# v0_6_2.net
KiCad netlist of a schematic drawn in EAGLE
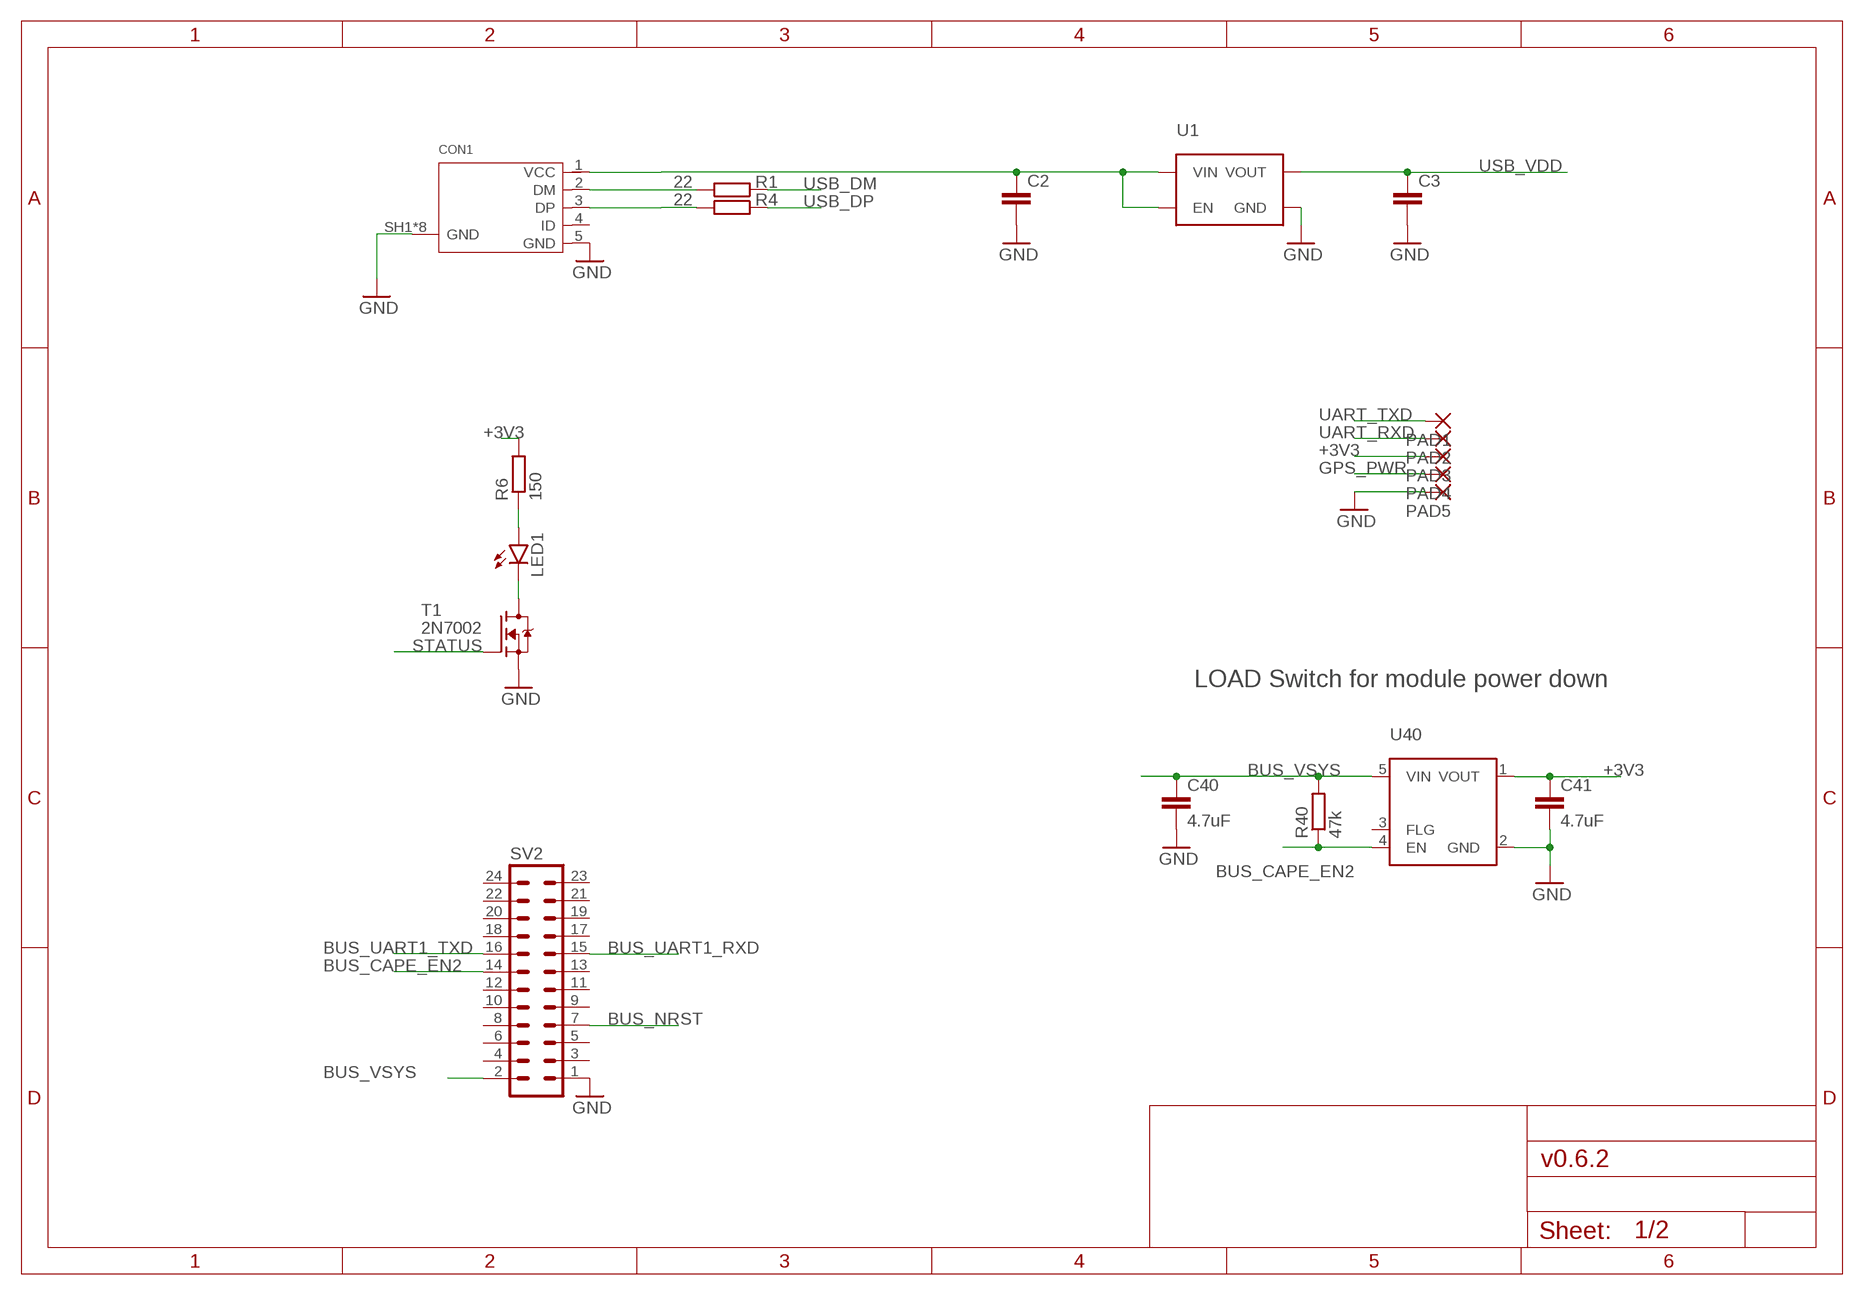
[diagram p0: schematic, sheet 1]
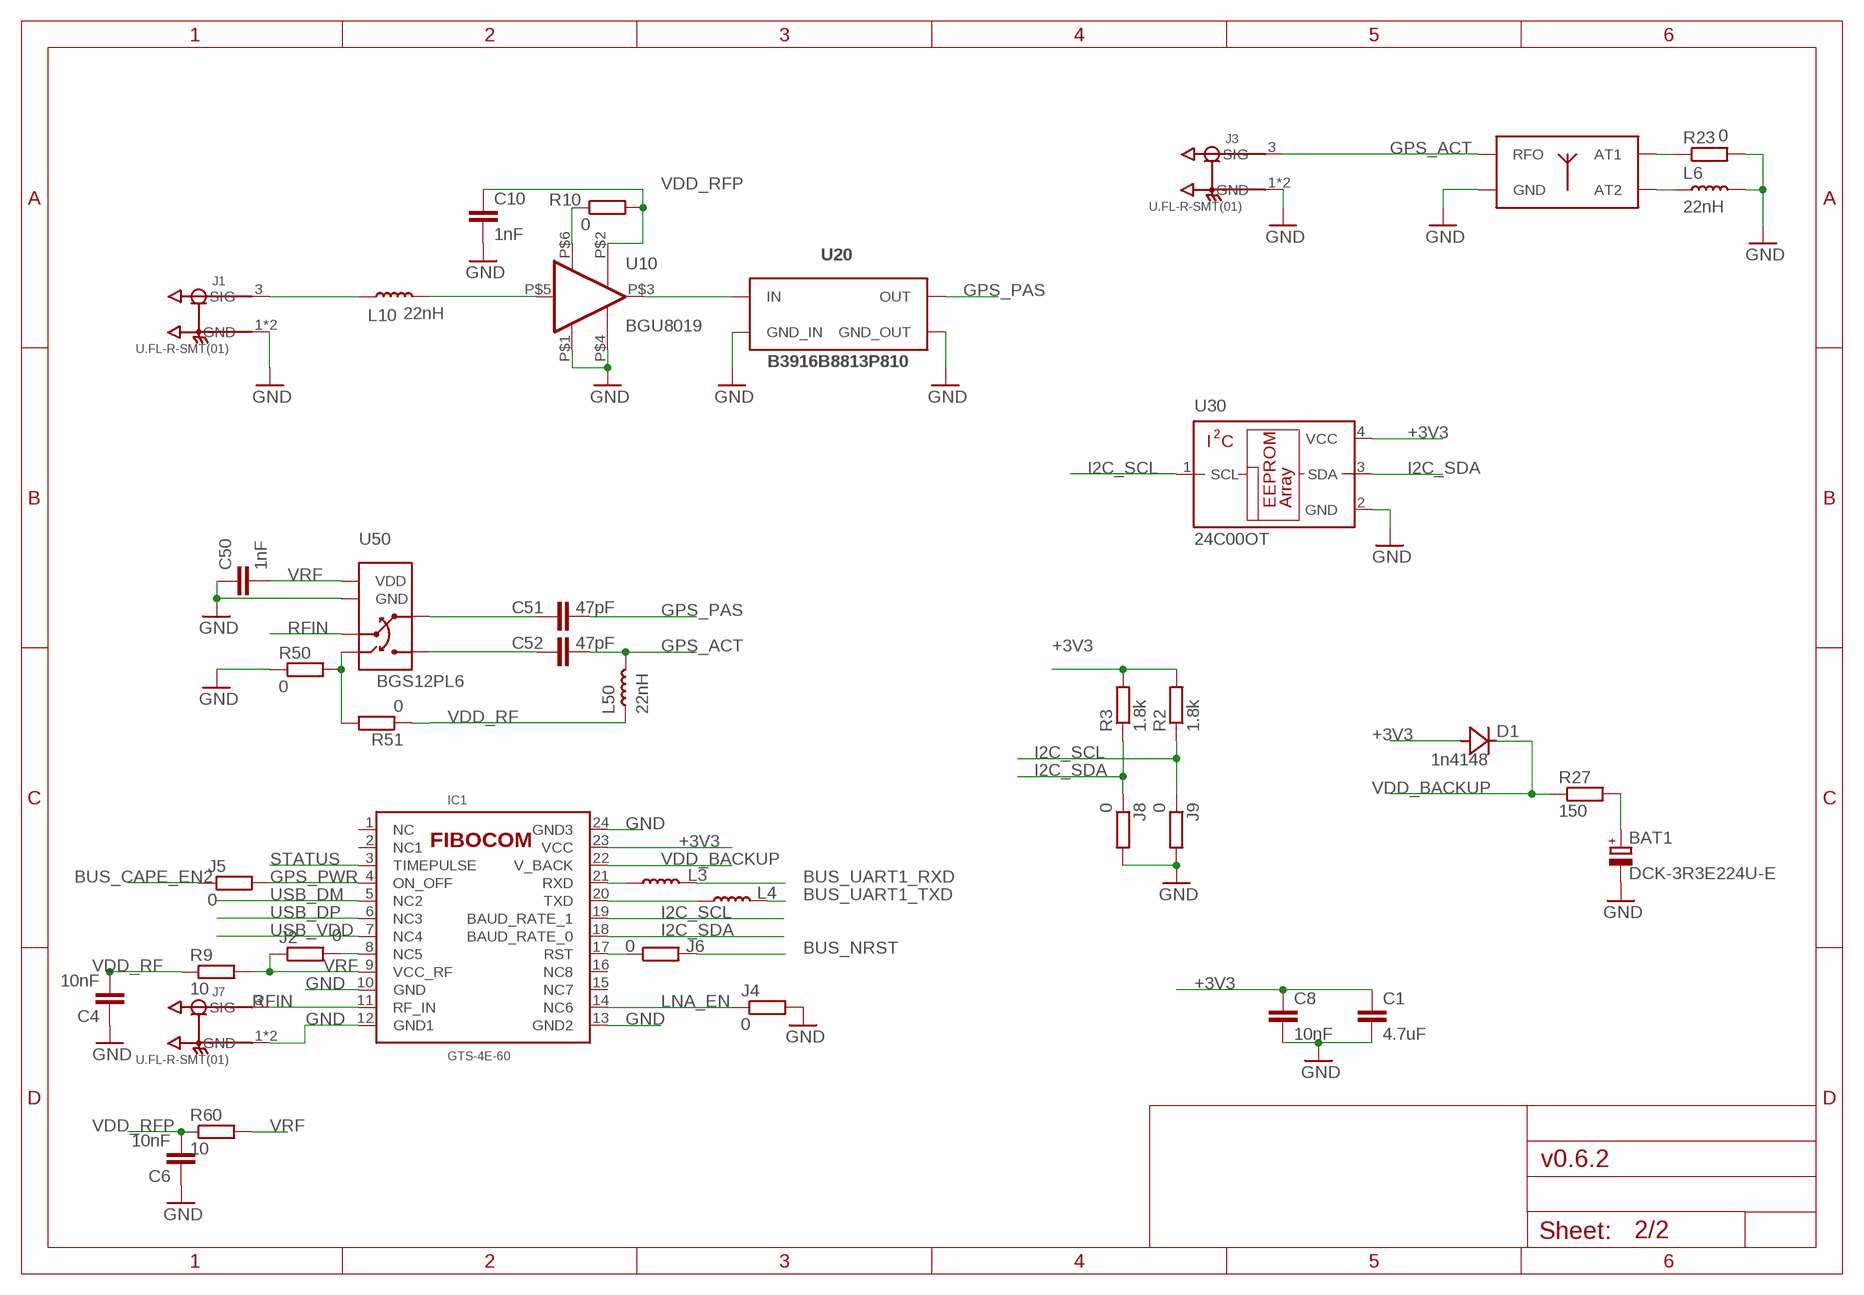
[diagram p1: schematic, sheet 2]

(export (version "E")
  (design (tool "Eeschema 10.0.6"))
  (components
    (comp (ref "ANT1")
      (value "M20047")
      (footprint "eagle-import:PCBCOMPONENT_1")
      (libsource (lib "eagle-import") (part "M20047"))
    )
    (comp (ref "BAT1")
      (value "DCK-3R3E224U-E")
      (footprint "eagle-import:621")
      (libsource (lib "eagle-import") (part "DCK-3R3E224U-E"))
    )
    (comp (ref "C1")
      (value "4.7uF")
      (footprint "eagle-import:C0603")
      (libsource (lib "eagle-import") (part "C-EUC0603"))
    )
    (comp (ref "C4")
      (value "10nF")
      (footprint "eagle-import:C0402K")
      (libsource (lib "eagle-import") (part "CAP-0402"))
    )
    (comp (ref "C6")
      (value "10nF")
      (footprint "eagle-import:C0402K")
      (libsource (lib "eagle-import") (part "CAP-0402"))
    )
    (comp (ref "C8")
      (value "10nF")
      (footprint "eagle-import:C0402K")
      (libsource (lib "eagle-import") (part "CAP-0402"))
    )
    (comp (ref "C10")
      (value "1nF")
      (footprint "eagle-import:C0402K")
      (libsource (lib "eagle-import") (part "CAP-0402"))
    )
    (comp (ref "C50")
      (value "1nF")
      (footprint "eagle-import:C0402K")
      (libsource (lib "eagle-import") (part "CAP-0402"))
    )
    (comp (ref "C51")
      (value "47pF")
      (footprint "eagle-import:C0402K")
      (libsource (lib "eagle-import") (part "CAP-0402"))
    )
    (comp (ref "C52")
      (value "47pF")
      (footprint "eagle-import:C0402K")
      (libsource (lib "eagle-import") (part "CAP-0402"))
    )
    (comp (ref "D1")
      (value "1n4148")
      (footprint "eagle-import:SOD323")
      (libsource (lib "eagle-import") (part "1N4148WS"))
    )
    (comp (ref "IC1")
      (value "GTS-4E-60")
      (footprint "eagle-import:_GTS_4E_60")
      (libsource (lib "eagle-import") (part "GTS-4E-60"))
    )
    (comp (ref "J1")
      (value "U.FL-R-SMT(01)")
      (footprint "eagle-import:HRS_U.FL-R-SMT(01)")
      (fields (field (name "MF") "Hirose") (field (name "MP") "U.FL-R-SMT_01_"))
      (libsource (lib "eagle-import") (part "U.FL-R-SMT(01)"))
    )
    (comp (ref "J2")
      (value "0")
      (footprint "eagle-import:R0402")
      (libsource (lib "eagle-import") (part "R-EU_R0402"))
    )
    (comp (ref "J3")
      (value "U.FL-R-SMT(01)")
      (footprint "eagle-import:HRS_U.FL-R-SMT(01)")
      (fields (field (name "MF") "Hirose") (field (name "MP") "U.FL-R-SMT_01_"))
      (libsource (lib "eagle-import") (part "U.FL-R-SMT(01)"))
    )
    (comp (ref "J4")
      (value "0")
      (footprint "eagle-import:R0402")
      (libsource (lib "eagle-import") (part "R-EU_R0402"))
    )
    (comp (ref "J5")
      (value "0")
      (footprint "eagle-import:R0402")
      (libsource (lib "eagle-import") (part "R-EU_R0402"))
    )
    (comp (ref "J6")
      (value "0")
      (footprint "eagle-import:R0402")
      (libsource (lib "eagle-import") (part "R-EU_R0402"))
    )
    (comp (ref "J7")
      (value "U.FL-R-SMT(01)")
      (footprint "eagle-import:HRS_U.FL-R-SMT(01)")
      (fields (field (name "MF") "Hirose") (field (name "MP") "U.FL-R-SMT_01_"))
      (libsource (lib "eagle-import") (part "U.FL-R-SMT(01)"))
    )
    (comp (ref "J8")
      (value "0")
      (footprint "eagle-import:R0402")
      (libsource (lib "eagle-import") (part "R-EU_R0402"))
    )
    (comp (ref "J9")
      (value "0")
      (footprint "eagle-import:R0402")
      (libsource (lib "eagle-import") (part "R-EU_R0402"))
    )
    (comp (ref "L3")
      (value "blm15")
      (footprint "eagle-import:L0402")
      (libsource (lib "eagle-import") (part "IND-0402"))
    )
    (comp (ref "L4")
      (value "blm15")
      (footprint "eagle-import:L0402")
      (libsource (lib "eagle-import") (part "IND-0402"))
    )
    (comp (ref "L6")
      (value "22nH")
      (footprint "eagle-import:L0402")
      (libsource (lib "eagle-import") (part "IND-0402"))
    )
    (comp (ref "L10")
      (value "22nH")
      (footprint "eagle-import:L0402")
      (libsource (lib "eagle-import") (part "IND-0402"))
    )
    (comp (ref "L50")
      (value "22nH")
      (footprint "eagle-import:L0402")
      (libsource (lib "eagle-import") (part "IND-0402"))
    )
    (comp (ref "R2")
      (value "1.8k")
      (footprint "eagle-import:R0402")
      (libsource (lib "eagle-import") (part "R-EU_R0402"))
    )
    (comp (ref "R3")
      (value "1.8k")
      (footprint "eagle-import:R0402")
      (libsource (lib "eagle-import") (part "R-EU_R0402"))
    )
    (comp (ref "R9")
      (value "10")
      (footprint "eagle-import:R0402")
      (libsource (lib "eagle-import") (part "R-EU_R0402"))
    )
    (comp (ref "R10")
      (value "0")
      (footprint "eagle-import:R0402")
      (libsource (lib "eagle-import") (part "R-EU_R0402"))
    )
    (comp (ref "R23")
      (value "0")
      (footprint "eagle-import:R0402")
      (libsource (lib "eagle-import") (part "R-EU_R0402"))
    )
    (comp (ref "R27")
      (value "150")
      (footprint "eagle-import:R0402")
      (libsource (lib "eagle-import") (part "R-EU_R0402"))
    )
    (comp (ref "R50")
      (value "0")
      (footprint "eagle-import:R0402")
      (libsource (lib "eagle-import") (part "R-EU_R0402"))
    )
    (comp (ref "R51")
      (value "0")
      (footprint "eagle-import:R0402")
      (libsource (lib "eagle-import") (part "R-EU_R0402"))
    )
    (comp (ref "R60")
      (value "10")
      (footprint "eagle-import:R0402")
      (libsource (lib "eagle-import") (part "R-EU_R0402"))
    )
    (comp (ref "U10")
      (value "BGU8019")
      (footprint "eagle-import:XSON6")
      (libsource (lib "eagle-import") (part "BGU8019"))
    )
    (comp (ref "U20")
      (value "B3916B8813P810")
      (footprint "eagle-import:XSON5")
      (libsource (lib "eagle-import") (part "B3916B8813P810"))
    )
    (comp (ref "U30")
      (value "24C00OT")
      (footprint "eagle-import:SOT23-5L")
      (fields (field (name "MF") "MICROCHIP") (field (name "MPN") "24C00T-I/OT"))
      (libsource (lib "eagle-import") (part "2400OTC"))
    )
    (comp (ref "U50")
      (value "BGS12PL6")
      (footprint "eagle-import:TSLP-6-4")
      (libsource (lib "eagle-import") (part "BGS12PL6"))
    )
    (comp (ref "C2")
      (value "C-EUC0603")
      (footprint "eagle-import:C0603")
      (libsource (lib "eagle-import") (part "C-EUC0603"))
    )
    (comp (ref "C3")
      (value "C-EUC0603")
      (footprint "eagle-import:C0603")
      (libsource (lib "eagle-import") (part "C-EUC0603"))
    )
    (comp (ref "C40")
      (value "4.7uF")
      (footprint "eagle-import:C0603")
      (libsource (lib "eagle-import") (part "C-EUC0603"))
    )
    (comp (ref "C41")
      (value "4.7uF")
      (footprint "eagle-import:C0603")
      (libsource (lib "eagle-import") (part "C-EUC0603"))
    )
    (comp (ref "CON1")
      (value "10118194-0001LF")
      (footprint "eagle-import:10118194")
      (libsource (lib "eagle-import") (part "10118194-0001LF"))
    )
    (comp (ref "LED1")
      (value "LEDCHIP-LED0603")
      (footprint "eagle-import:CHIP-LED0603")
      (libsource (lib "eagle-import") (part "LEDCHIP-LED0603"))
    )
    (comp (ref "PAD1")
      (value "1,6/0,9")
      (footprint "eagle-import:1,6_0,9")
      (libsource (lib "eagle-import") (part "1,6/0,9"))
    )
    (comp (ref "PAD2")
      (value "1,6/0,9")
      (footprint "eagle-import:1,6_0,9")
      (libsource (lib "eagle-import") (part "1,6/0,9"))
    )
    (comp (ref "PAD3")
      (value "1,6/0,9")
      (footprint "eagle-import:1,6_0,9")
      (libsource (lib "eagle-import") (part "1,6/0,9"))
    )
    (comp (ref "PAD4")
      (value "1,6/0,9")
      (footprint "eagle-import:1,6_0,9")
      (libsource (lib "eagle-import") (part "1,6/0,9"))
    )
    (comp (ref "PAD5")
      (value "1,6/0,9")
      (footprint "eagle-import:1,6_0,9")
      (libsource (lib "eagle-import") (part "1,6/0,9"))
    )
    (comp (ref "R1")
      (value "22")
      (footprint "eagle-import:R0402")
      (libsource (lib "eagle-import") (part "R-EU_R0402"))
    )
    (comp (ref "R4")
      (value "22")
      (footprint "eagle-import:R0402")
      (libsource (lib "eagle-import") (part "R-EU_R0402"))
    )
    (comp (ref "R6")
      (value "150")
      (footprint "eagle-import:R0402")
      (libsource (lib "eagle-import") (part "R-EU_R0402"))
    )
    (comp (ref "R40")
      (value "47k")
      (footprint "eagle-import:R0402")
      (libsource (lib "eagle-import") (part "R-EU_R0402"))
    )
    (comp (ref "SV2")
      (value "MA12-2")
      (footprint "eagle-import:MA12-2")
      (libsource (lib "eagle-import") (part "MA12-2"))
    )
    (comp (ref "T1")
      (value "2N7002")
      (footprint "eagle-import:SOT95P240X110-3")
      (libsource (lib "eagle-import") (part "2N7002"))
    )
    (comp (ref "U1")
      (value "MIC94310")
      (footprint "eagle-import:SOT95P280X110-5")
      (libsource (lib "eagle-import") (part "MIC94310"))
    )
    (comp (ref "U40")
      (value "AP22802b")
      (footprint "eagle-import:SOT25")
      (libsource (lib "eagle-import") (part "AP22802"))
    )
  )
  (nets
    (net (code "1") (name "+3V3") (class "Default")
      (node (ref "C1") (pin "1") (pinfunction "1_1") (pintype "passive"))
      (node (ref "C41") (pin "1") (pinfunction "1_1") (pintype "passive"))
      (node (ref "C8") (pin "1") (pinfunction "1_1") (pintype "passive"))
      (node (ref "D1") (pin "A") (pinfunction "A_A") (pintype "passive"))
      (node (ref "IC1") (pin "23") (pinfunction "VCC_23") (pintype "bidirectional"))
      (node (ref "PAD3") (pin "1") (pinfunction "P_1") (pintype "passive"))
      (node (ref "R2") (pin "2") (pinfunction "2_2") (pintype "passive"))
      (node (ref "R3") (pin "2") (pinfunction "2_2") (pintype "passive"))
      (node (ref "R6") (pin "2") (pinfunction "2_2") (pintype "passive"))
      (node (ref "U30") (pin "4") (pinfunction "VCC_4") (pintype "power_in"))
      (node (ref "U40") (pin "1") (pinfunction "VOUT_1") (pintype "bidirectional"))
    )
    (net (code "2") (name "BUS_CAPE_EN2") (class "Default")
      (node (ref "J5") (pin "1") (pinfunction "1_1") (pintype "passive"))
      (node (ref "R40") (pin "1") (pinfunction "1_1") (pintype "passive"))
      (node (ref "SV2") (pin "14") (pinfunction "14_14") (pintype "passive"))
      (node (ref "U40") (pin "4") (pinfunction "EN_4") (pintype "bidirectional"))
    )
    (net (code "3") (name "BUS_NRST") (class "Default")
      (node (ref "J6") (pin "2") (pinfunction "2_2") (pintype "passive"))
      (node (ref "SV2") (pin "7") (pinfunction "7_7") (pintype "passive"))
    )
    (net (code "4") (name "BUS_UART1_RXD") (class "Default")
      (node (ref "L3") (pin "2") (pinfunction "2_2") (pintype "passive"))
      (node (ref "SV2") (pin "15") (pinfunction "15_15") (pintype "passive"))
    )
    (net (code "5") (name "BUS_UART1_TXD") (class "Default")
      (node (ref "L4") (pin "2") (pinfunction "2_2") (pintype "passive"))
      (node (ref "SV2") (pin "16") (pinfunction "16_16") (pintype "passive"))
    )
    (net (code "6") (name "BUS_VSYS") (class "Default")
      (node (ref "C40") (pin "1") (pinfunction "1_1") (pintype "passive"))
      (node (ref "R40") (pin "2") (pinfunction "2_2") (pintype "passive"))
      (node (ref "SV2") (pin "2") (pinfunction "2_2") (pintype "passive"))
      (node (ref "U40") (pin "5") (pinfunction "VIN_5") (pintype "bidirectional"))
    )
    (net (code "7") (name "GND") (class "Default")
      (node (ref "ANT1") (pin "2") (pinfunction "GND_2") (pintype "power_in"))
      (node (ref "ANT1") (pin "3") (pinfunction "GND_3") (pintype "power_in"))
      (node (ref "ANT1") (pin "4") (pinfunction "GND_4") (pintype "power_in"))
      (node (ref "BAT1") (pin "-") (pinfunction "-_-") (pintype "passive"))
      (node (ref "C1") (pin "2") (pinfunction "2_2") (pintype "passive"))
      (node (ref "C10") (pin "2") (pinfunction "2_2") (pintype "passive"))
      (node (ref "C2") (pin "2") (pinfunction "2_2") (pintype "passive"))
      (node (ref "C3") (pin "2") (pinfunction "2_2") (pintype "passive"))
      (node (ref "C4") (pin "1") (pinfunction "1_1") (pintype "passive"))
      (node (ref "C40") (pin "2") (pinfunction "2_2") (pintype "passive"))
      (node (ref "C41") (pin "2") (pinfunction "2_2") (pintype "passive"))
      (node (ref "C50") (pin "1") (pinfunction "1_1") (pintype "passive"))
      (node (ref "C6") (pin "1") (pinfunction "1_1") (pintype "passive"))
      (node (ref "C8") (pin "2") (pinfunction "2_2") (pintype "passive"))
      (node (ref "CON1") (pin "5") (pinfunction "GND_5") (pintype "bidirectional"))
      (node (ref "CON1") (pin "SH1") (pinfunction "GND_SH1") (pintype "bidirectional"))
      (node (ref "CON1") (pin "SH2") (pinfunction "GND_SH2") (pintype "bidirectional"))
      (node (ref "CON1") (pin "SH3") (pinfunction "GND_SH3") (pintype "bidirectional"))
      (node (ref "CON1") (pin "SH4") (pinfunction "GND_SH4") (pintype "bidirectional"))
      (node (ref "CON1") (pin "SH5") (pinfunction "GND_SH5") (pintype "bidirectional"))
      (node (ref "CON1") (pin "SH6") (pinfunction "GND_SH6") (pintype "bidirectional"))
      (node (ref "CON1") (pin "SH7") (pinfunction "GND_SH7") (pintype "bidirectional"))
      (node (ref "CON1") (pin "SH8") (pinfunction "GND_SH8") (pintype "bidirectional"))
      (node (ref "IC1") (pin "10") (pinfunction "GND_10") (pintype "bidirectional"))
      (node (ref "IC1") (pin "12") (pinfunction "GND1_12") (pintype "bidirectional"))
      (node (ref "IC1") (pin "13") (pinfunction "GND2_13") (pintype "bidirectional"))
      (node (ref "IC1") (pin "24") (pinfunction "GND3_24") (pintype "bidirectional"))
      (node (ref "J1") (pin "1") (pinfunction "GND_1") (pintype "passive"))
      (node (ref "J1") (pin "2") (pinfunction "GND_2") (pintype "passive"))
      (node (ref "J3") (pin "1") (pinfunction "GND_1") (pintype "passive"))
      (node (ref "J3") (pin "2") (pinfunction "GND_2") (pintype "passive"))
      (node (ref "J4") (pin "2") (pinfunction "2_2") (pintype "passive"))
      (node (ref "J7") (pin "1") (pinfunction "GND_1") (pintype "passive"))
      (node (ref "J7") (pin "2") (pinfunction "GND_2") (pintype "passive"))
      (node (ref "J8") (pin "2") (pinfunction "2_2") (pintype "passive"))
      (node (ref "J9") (pin "2") (pinfunction "2_2") (pintype "passive"))
      (node (ref "L6") (pin "2") (pinfunction "2_2") (pintype "passive"))
      (node (ref "PAD5") (pin "1") (pinfunction "P_1") (pintype "passive"))
      (node (ref "R23") (pin "2") (pinfunction "2_2") (pintype "passive"))
      (node (ref "R50") (pin "1") (pinfunction "1_1") (pintype "passive"))
      (node (ref "SV2") (pin "1") (pinfunction "1_1") (pintype "passive"))
      (node (ref "T1") (pin "2") (pinfunction "S_2") (pintype "passive"))
      (node (ref "U1") (pin "2") (pinfunction "GND_2") (pintype "bidirectional"))
      (node (ref "U10") (pin "P$1") (pinfunction "GND_P$1") (pintype "power_in"))
      (node (ref "U10") (pin "P$4") (pinfunction "GND_RF_P$4") (pintype "passive"))
      (node (ref "U20") (pin "2") (pinfunction "GND_IN_2") (pintype "bidirectional"))
      (node (ref "U20") (pin "3") (pinfunction "GND_OUT_3") (pintype "bidirectional"))
      (node (ref "U20") (pin "5") (pinfunction "GND_IN_5") (pintype "bidirectional"))
      (node (ref "U30") (pin "2") (pinfunction "GND_2") (pintype "power_in"))
      (node (ref "U40") (pin "2") (pinfunction "GND_2") (pintype "bidirectional"))
      (node (ref "U50") (pin "P$2") (pinfunction "GND_P$2") (pintype "power_in"))
    )
    (net (code "8") (name "GPS_ACT") (class "Default")
      (node (ref "ANT1") (pin "5") (pinfunction "RFO_5") (pintype "input"))
      (node (ref "C52") (pin "2") (pinfunction "2_2") (pintype "passive"))
      (node (ref "J3") (pin "3") (pinfunction "SIG_3") (pintype "passive"))
      (node (ref "L50") (pin "2") (pinfunction "2_2") (pintype "passive"))
    )
    (net (code "9") (name "GPS_PAS") (class "Default")
      (node (ref "C51") (pin "2") (pinfunction "2_2") (pintype "passive"))
      (node (ref "U20") (pin "4") (pinfunction "OUT_4") (pintype "bidirectional"))
    )
    (net (code "10") (name "GPS_PWR") (class "Default")
      (node (ref "IC1") (pin "4") (pinfunction "ON_OFF_4") (pintype "bidirectional"))
      (node (ref "J5") (pin "2") (pinfunction "2_2") (pintype "passive"))
      (node (ref "PAD4") (pin "1") (pinfunction "P_1") (pintype "passive"))
    )
    (net (code "11") (name "I2C_SCL") (class "Default")
      (node (ref "IC1") (pin "19") (pinfunction "BAUD_RATE_1_19") (pintype "bidirectional"))
      (node (ref "J9") (pin "1") (pinfunction "1_1") (pintype "passive"))
      (node (ref "R2") (pin "1") (pinfunction "1_1") (pintype "passive"))
      (node (ref "U30") (pin "1") (pinfunction "SCL_1") (pintype "input"))
    )
    (net (code "12") (name "I2C_SDA") (class "Default")
      (node (ref "IC1") (pin "18") (pinfunction "BAUD_RATE_0_18") (pintype "bidirectional"))
      (node (ref "J8") (pin "1") (pinfunction "1_1") (pintype "passive"))
      (node (ref "R3") (pin "1") (pinfunction "1_1") (pintype "passive"))
      (node (ref "U30") (pin "3") (pinfunction "SDA_3") (pintype "bidirectional"))
    )
    (net (code "13") (name "LNA_EN") (class "Default")
      (node (ref "IC1") (pin "14") (pinfunction "NC6_14") (pintype "bidirectional"))
      (node (ref "J4") (pin "1") (pinfunction "1_1") (pintype "passive"))
    )
    (net (code "14") (name "Net-(ANT1-AT1)") (class "Default")
      (node (ref "ANT1") (pin "1") (pinfunction "AT1_1") (pintype "bidirectional"))
      (node (ref "R23") (pin "1") (pinfunction "1_1") (pintype "passive"))
    )
    (net (code "15") (name "Net-(ANT1-AT2)") (class "Default")
      (node (ref "ANT1") (pin "6") (pinfunction "AT2_6") (pintype "bidirectional"))
      (node (ref "L6") (pin "1") (pinfunction "1_1") (pintype "passive"))
    )
    (net (code "16") (name "Net-(BAT1-Pad+)") (class "Default")
      (node (ref "BAT1") (pin "+") (pinfunction "+_+") (pintype "passive"))
      (node (ref "R27") (pin "2") (pinfunction "2_2") (pintype "passive"))
    )
    (net (code "17") (name "Net-(CON1-DM)") (class "Default")
      (node (ref "CON1") (pin "2") (pinfunction "DM_2") (pintype "bidirectional"))
      (node (ref "R1") (pin "2") (pinfunction "2_2") (pintype "passive"))
    )
    (net (code "18") (name "Net-(CON1-DP)") (class "Default")
      (node (ref "CON1") (pin "3") (pinfunction "DP_3") (pintype "bidirectional"))
      (node (ref "R4") (pin "2") (pinfunction "2_2") (pintype "passive"))
    )
    (net (code "19") (name "Net-(CON1-VCC)") (class "Default")
      (node (ref "C2") (pin "1") (pinfunction "1_1") (pintype "passive"))
      (node (ref "CON1") (pin "1") (pinfunction "VCC_1") (pintype "bidirectional"))
      (node (ref "U1") (pin "1") (pinfunction "VIN_1") (pintype "bidirectional"))
      (node (ref "U1") (pin "3") (pinfunction "EN_3") (pintype "bidirectional"))
    )
    (net (code "20") (name "Net-(IC1-NC5)") (class "Default")
      (node (ref "IC1") (pin "8") (pinfunction "NC5_8") (pintype "bidirectional"))
      (node (ref "J2") (pin "2") (pinfunction "2_2") (pintype "passive"))
    )
    (net (code "21") (name "Net-(IC1-RST)") (class "Default")
      (node (ref "IC1") (pin "17") (pinfunction "RST_17") (pintype "bidirectional"))
      (node (ref "J6") (pin "1") (pinfunction "1_1") (pintype "passive"))
    )
    (net (code "22") (name "Net-(J1-SIG)") (class "Default")
      (node (ref "J1") (pin "3") (pinfunction "SIG_3") (pintype "passive"))
      (node (ref "L10") (pin "1") (pinfunction "1_1") (pintype "passive"))
    )
    (net (code "23") (name "Net-(LED1-PadA)") (class "Default")
      (node (ref "LED1") (pin "A") (pinfunction "A_A") (pintype "passive"))
      (node (ref "R6") (pin "1") (pinfunction "1_1") (pintype "passive"))
    )
    (net (code "24") (name "Net-(T1-D)") (class "Default")
      (node (ref "LED1") (pin "C") (pinfunction "C_C") (pintype "passive"))
      (node (ref "T1") (pin "3") (pinfunction "D_3") (pintype "passive"))
    )
    (net (code "25") (name "Net-(U10-ENABLE)") (class "Default")
      (node (ref "R10") (pin "1") (pinfunction "1_1") (pintype "passive"))
      (node (ref "U10") (pin "P$6") (pinfunction "ENABLE_P$6") (pintype "power_in"))
    )
    (net (code "26") (name "Net-(U10-RF_IN)") (class "Default")
      (node (ref "L10") (pin "2") (pinfunction "2_2") (pintype "passive"))
      (node (ref "U10") (pin "P$5") (pinfunction "RF_IN_P$5") (pintype "input"))
    )
    (net (code "27") (name "Net-(U10-RF_OUT)") (class "Default")
      (node (ref "U10") (pin "P$3") (pinfunction "RF_OUT_P$3") (pintype "output"))
      (node (ref "U20") (pin "1") (pinfunction "IN_1") (pintype "bidirectional"))
    )
    (net (code "28") (name "Net-(U50-P$4)") (class "Default")
      (node (ref "R50") (pin "2") (pinfunction "2_2") (pintype "passive"))
      (node (ref "R51") (pin "2") (pinfunction "2_2") (pintype "passive"))
      (node (ref "U50") (pin "P$6") (pinfunction "P$4_P$6") (pintype "bidirectional"))
    )
    (net (code "29") (name "Net-(U50-RF1)") (class "Default")
      (node (ref "C51") (pin "1") (pinfunction "1_1") (pintype "passive"))
      (node (ref "U50") (pin "P$3") (pinfunction "RF1_P$3") (pintype "bidirectional"))
    )
    (net (code "30") (name "Net-(U50-RF2)") (class "Default")
      (node (ref "C52") (pin "1") (pinfunction "1_1") (pintype "passive"))
      (node (ref "U50") (pin "P$1") (pinfunction "RF2_P$1") (pintype "bidirectional"))
    )
    (net (code "31") (name "RFIN") (class "Default")
      (node (ref "IC1") (pin "11") (pinfunction "RF_IN_11") (pintype "bidirectional"))
      (node (ref "J7") (pin "3") (pinfunction "SIG_3") (pintype "passive"))
      (node (ref "U50") (pin "P$5") (pinfunction "RFIN_P$5") (pintype "bidirectional"))
    )
    (net (code "32") (name "STATUS") (class "Default")
      (node (ref "IC1") (pin "3") (pinfunction "TIMEPULSE_3") (pintype "bidirectional"))
      (node (ref "T1") (pin "1") (pinfunction "G_1") (pintype "passive"))
    )
    (net (code "33") (name "UART_RXD") (class "Default")
      (node (ref "IC1") (pin "20") (pinfunction "TXD_20") (pintype "bidirectional"))
      (node (ref "L4") (pin "1") (pinfunction "1_1") (pintype "passive"))
      (node (ref "PAD2") (pin "1") (pinfunction "P_1") (pintype "passive"))
    )
    (net (code "34") (name "UART_TXD") (class "Default")
      (node (ref "IC1") (pin "21") (pinfunction "RXD_21") (pintype "bidirectional"))
      (node (ref "L3") (pin "1") (pinfunction "1_1") (pintype "passive"))
      (node (ref "PAD1") (pin "1") (pinfunction "P_1") (pintype "passive"))
    )
    (net (code "35") (name "USB_DM") (class "Default")
      (node (ref "IC1") (pin "5") (pinfunction "NC2_5") (pintype "bidirectional"))
      (node (ref "R1") (pin "1") (pinfunction "1_1") (pintype "passive"))
    )
    (net (code "36") (name "USB_DP") (class "Default")
      (node (ref "IC1") (pin "6") (pinfunction "NC3_6") (pintype "bidirectional"))
      (node (ref "R4") (pin "1") (pinfunction "1_1") (pintype "passive"))
    )
    (net (code "37") (name "USB_VDD") (class "Default")
      (node (ref "C3") (pin "1") (pinfunction "1_1") (pintype "passive"))
      (node (ref "IC1") (pin "7") (pinfunction "NC4_7") (pintype "bidirectional"))
      (node (ref "U1") (pin "5") (pinfunction "VOUT_5") (pintype "bidirectional"))
    )
    (net (code "38") (name "VDD_BACKUP") (class "Default")
      (node (ref "D1") (pin "K") (pinfunction "C_K") (pintype "passive"))
      (node (ref "IC1") (pin "22") (pinfunction "V_BACK_22") (pintype "bidirectional"))
      (node (ref "R27") (pin "1") (pinfunction "1_1") (pintype "passive"))
    )
    (net (code "39") (name "VDD_RF") (class "Default")
      (node (ref "C4") (pin "2") (pinfunction "2_2") (pintype "passive"))
      (node (ref "L50") (pin "1") (pinfunction "1_1") (pintype "passive"))
      (node (ref "R51") (pin "1") (pinfunction "1_1") (pintype "passive"))
      (node (ref "R9") (pin "1") (pinfunction "1_1") (pintype "passive"))
    )
    (net (code "40") (name "VDD_RFP") (class "Default")
      (node (ref "C10") (pin "1") (pinfunction "1_1") (pintype "passive"))
      (node (ref "C6") (pin "2") (pinfunction "2_2") (pintype "passive"))
      (node (ref "R10") (pin "2") (pinfunction "2_2") (pintype "passive"))
      (node (ref "R60") (pin "1") (pinfunction "1_1") (pintype "passive"))
      (node (ref "U10") (pin "P$2") (pinfunction "VCC_P$2") (pintype "passive"))
    )
    (net (code "41") (name "VRF") (class "Default")
      (node (ref "C50") (pin "2") (pinfunction "2_2") (pintype "passive"))
      (node (ref "IC1") (pin "9") (pinfunction "VCC_RF_9") (pintype "bidirectional"))
      (node (ref "J2") (pin "1") (pinfunction "1_1") (pintype "passive"))
      (node (ref "R60") (pin "2") (pinfunction "2_2") (pintype "passive"))
      (node (ref "R9") (pin "2") (pinfunction "2_2") (pintype "passive"))
      (node (ref "U50") (pin "P$4") (pinfunction "VDD_P$4") (pintype "power_in"))
    )
    (net (code "42") (name "unconnected-(CON1-ID-Pad4)") (class "Default")
      (node (ref "CON1") (pin "4") (pinfunction "ID_4") (pintype "bidirectional"))
    )
    (net (code "43") (name "unconnected-(IC1-NC-Pad1)") (class "Default")
      (node (ref "IC1") (pin "1") (pinfunction "NC_1") (pintype "bidirectional"))
    )
    (net (code "44") (name "unconnected-(IC1-NC1-Pad2)") (class "Default")
      (node (ref "IC1") (pin "2") (pinfunction "NC1_2") (pintype "bidirectional"))
    )
    (net (code "45") (name "unconnected-(IC1-NC7-Pad15)") (class "Default")
      (node (ref "IC1") (pin "15") (pinfunction "NC7_15") (pintype "bidirectional"))
    )
    (net (code "46") (name "unconnected-(IC1-NC8-Pad16)") (class "Default")
      (node (ref "IC1") (pin "16") (pinfunction "NC8_16") (pintype "bidirectional"))
    )
    (net (code "47") (name "unconnected-(SV2-Pad3)") (class "Default")
      (node (ref "SV2") (pin "3") (pinfunction "3_3") (pintype "passive"))
    )
    (net (code "48") (name "unconnected-(SV2-Pad4)") (class "Default")
      (node (ref "SV2") (pin "4") (pinfunction "4_4") (pintype "passive"))
    )
    (net (code "49") (name "unconnected-(SV2-Pad5)") (class "Default")
      (node (ref "SV2") (pin "5") (pinfunction "5_5") (pintype "passive"))
    )
    (net (code "50") (name "unconnected-(SV2-Pad6)") (class "Default")
      (node (ref "SV2") (pin "6") (pinfunction "6_6") (pintype "passive"))
    )
    (net (code "51") (name "unconnected-(SV2-Pad8)") (class "Default")
      (node (ref "SV2") (pin "8") (pinfunction "8_8") (pintype "passive"))
    )
    (net (code "52") (name "unconnected-(SV2-Pad9)") (class "Default")
      (node (ref "SV2") (pin "9") (pinfunction "9_9") (pintype "passive"))
    )
    (net (code "53") (name "unconnected-(SV2-Pad10)") (class "Default")
      (node (ref "SV2") (pin "10") (pinfunction "10_10") (pintype "passive"))
    )
    (net (code "54") (name "unconnected-(SV2-Pad11)") (class "Default")
      (node (ref "SV2") (pin "11") (pinfunction "11_11") (pintype "passive"))
    )
    (net (code "55") (name "unconnected-(SV2-Pad12)") (class "Default")
      (node (ref "SV2") (pin "12") (pinfunction "12_12") (pintype "passive"))
    )
    (net (code "56") (name "unconnected-(SV2-Pad13)") (class "Default")
      (node (ref "SV2") (pin "13") (pinfunction "13_13") (pintype "passive"))
    )
    (net (code "57") (name "unconnected-(SV2-Pad17)") (class "Default")
      (node (ref "SV2") (pin "17") (pinfunction "17_17") (pintype "passive"))
    )
    (net (code "58") (name "unconnected-(SV2-Pad18)") (class "Default")
      (node (ref "SV2") (pin "18") (pinfunction "18_18") (pintype "passive"))
    )
    (net (code "59") (name "unconnected-(SV2-Pad19)") (class "Default")
      (node (ref "SV2") (pin "19") (pinfunction "19_19") (pintype "passive"))
    )
    (net (code "60") (name "unconnected-(SV2-Pad20)") (class "Default")
      (node (ref "SV2") (pin "20") (pinfunction "20_20") (pintype "passive"))
    )
    (net (code "61") (name "unconnected-(SV2-Pad21)") (class "Default")
      (node (ref "SV2") (pin "21") (pinfunction "21_21") (pintype "passive"))
    )
    (net (code "62") (name "unconnected-(SV2-Pad22)") (class "Default")
      (node (ref "SV2") (pin "22") (pinfunction "22_22") (pintype "passive"))
    )
    (net (code "63") (name "unconnected-(SV2-Pad23)") (class "Default")
      (node (ref "SV2") (pin "23") (pinfunction "23_23") (pintype "passive"))
    )
    (net (code "64") (name "unconnected-(SV2-Pad24)") (class "Default")
      (node (ref "SV2") (pin "24") (pinfunction "24_24") (pintype "passive"))
    )
    (net (code "65") (name "unconnected-(U40-FLG-Pad3)") (class "Default")
      (node (ref "U40") (pin "3") (pinfunction "FLG_3") (pintype "bidirectional"))
    )
  )
)
